# stoneWeather.net
KiCad netlist of a schematic drawn in EAGLE
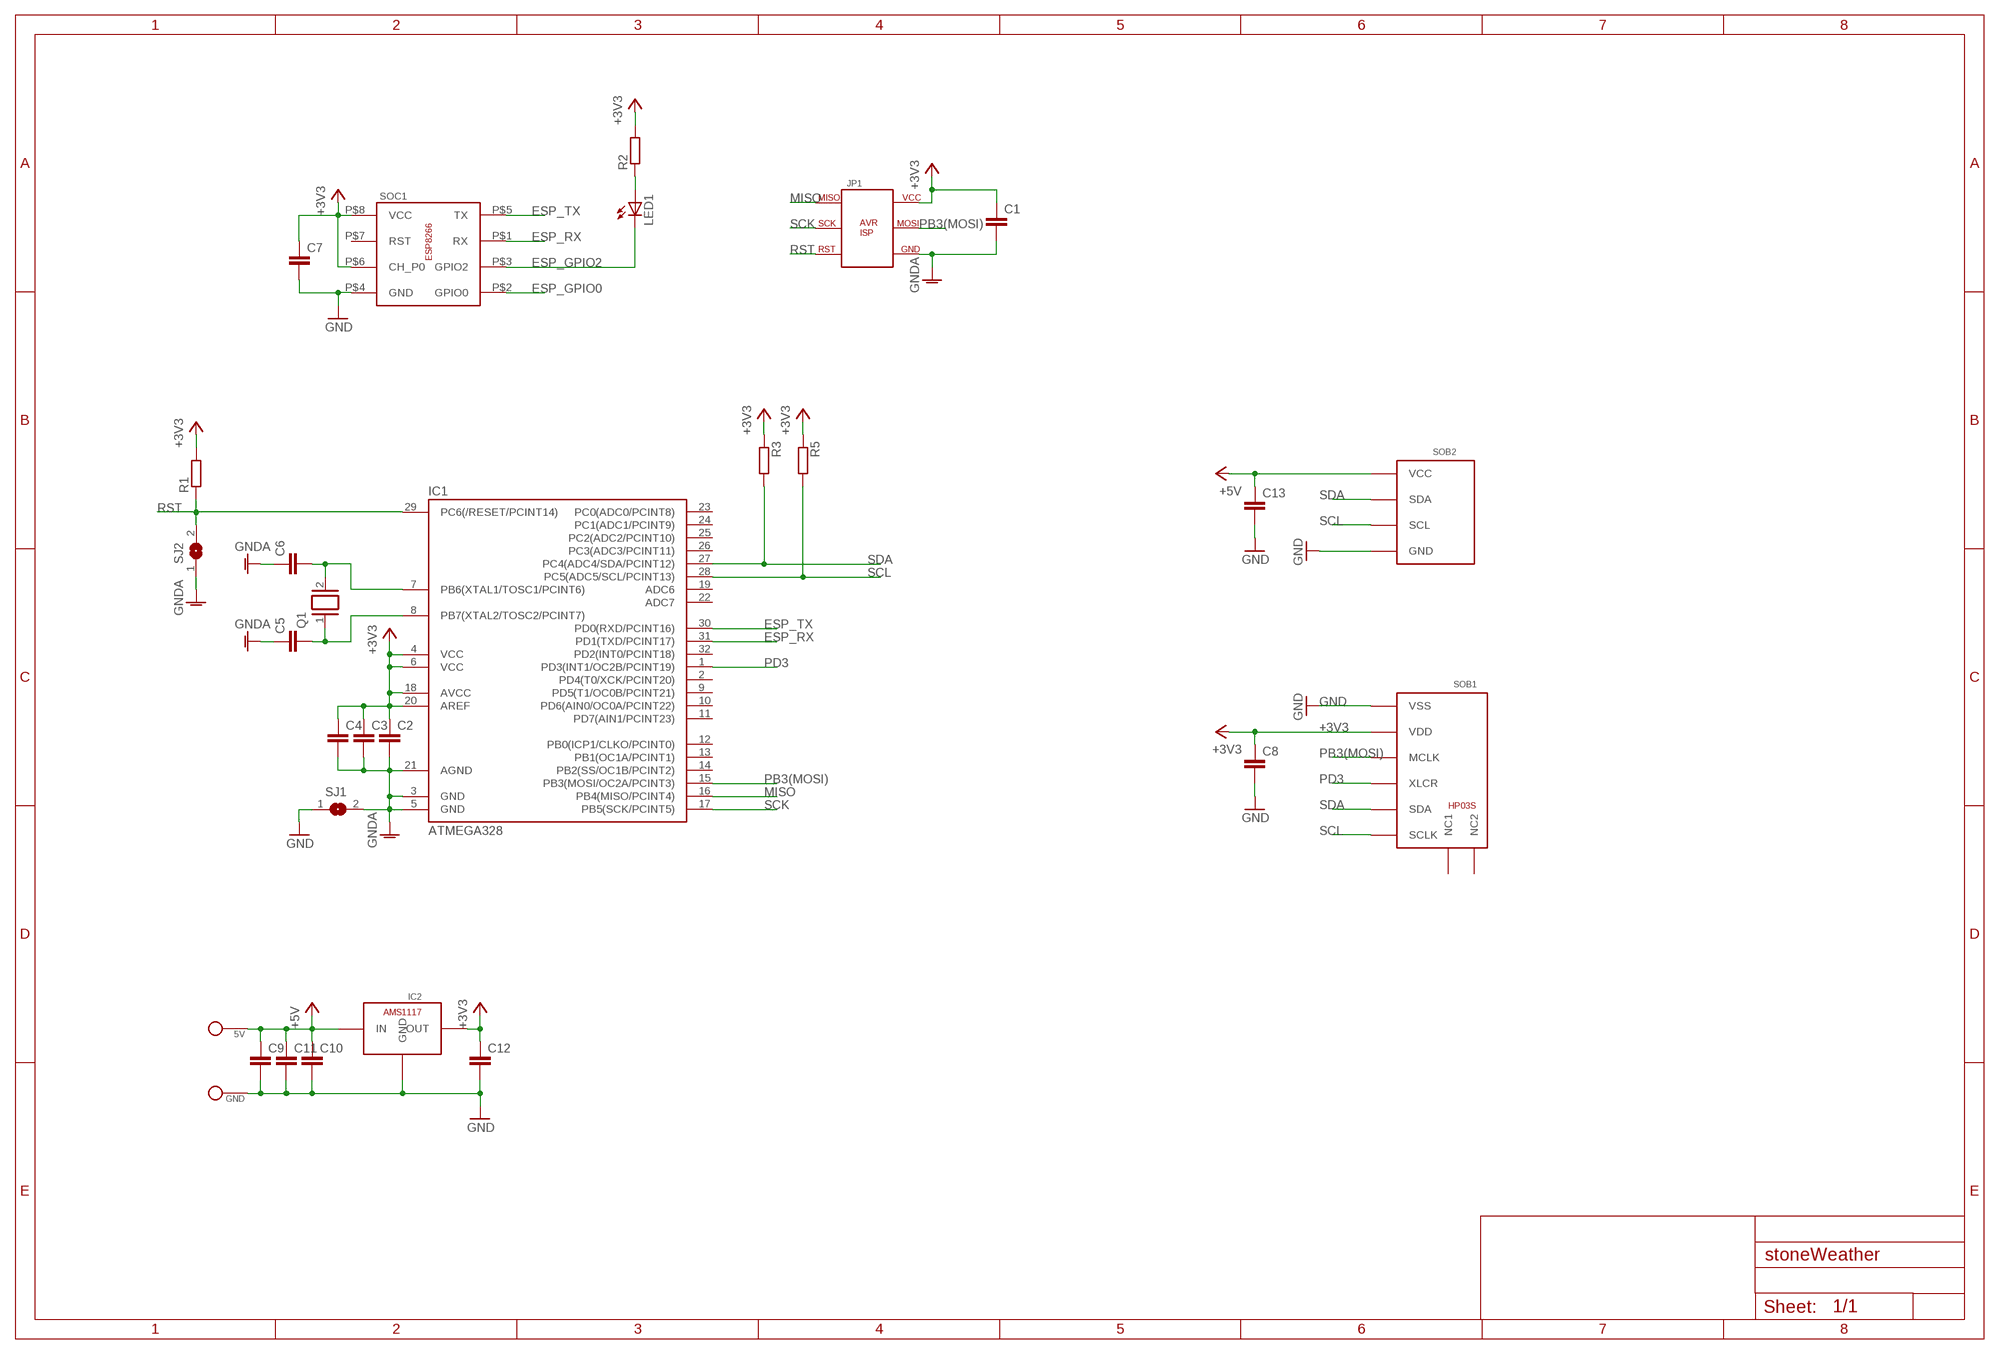
[diagram p0: schematic, sheet 1]

(export (version "E")
  (design (tool "Eeschema 10.0.6"))
  (components
    (comp (ref "5V")
      (value "PAD_254X508")
      (footprint "eagle-import:PAD_254X508")
      (libsource (lib "eagle-import") (part "PAD_254X508"))
    )
    (comp (ref "C1")
      (value "C-EUC0805")
      (footprint "eagle-import:C0805")
      (libsource (lib "eagle-import") (part "C-EUC0805"))
    )
    (comp (ref "C2")
      (value "C-EUC0805")
      (footprint "eagle-import:C0805")
      (libsource (lib "eagle-import") (part "C-EUC0805"))
    )
    (comp (ref "C3")
      (value "C-EUC0805")
      (footprint "eagle-import:C0805")
      (libsource (lib "eagle-import") (part "C-EUC0805"))
    )
    (comp (ref "C4")
      (value "C-EUC0805")
      (footprint "eagle-import:C0805")
      (libsource (lib "eagle-import") (part "C-EUC0805"))
    )
    (comp (ref "C5")
      (value "C-EUC0805")
      (footprint "eagle-import:C0805")
      (libsource (lib "eagle-import") (part "C-EUC0805"))
    )
    (comp (ref "C6")
      (value "C-EUC0805")
      (footprint "eagle-import:C0805")
      (libsource (lib "eagle-import") (part "C-EUC0805"))
    )
    (comp (ref "C7")
      (value "C-EUC0805")
      (footprint "eagle-import:C0805")
      (libsource (lib "eagle-import") (part "C-EUC0805"))
    )
    (comp (ref "C8")
      (value "C-EUC0805")
      (footprint "eagle-import:C0805")
      (libsource (lib "eagle-import") (part "C-EUC0805"))
    )
    (comp (ref "C9")
      (value "C-EUC0805")
      (footprint "eagle-import:C0805")
      (libsource (lib "eagle-import") (part "C-EUC0805"))
    )
    (comp (ref "C10")
      (value "C-EUC0805")
      (footprint "eagle-import:C0805")
      (libsource (lib "eagle-import") (part "C-EUC0805"))
    )
    (comp (ref "C11")
      (value "C-EUC0805")
      (footprint "eagle-import:C0805")
      (libsource (lib "eagle-import") (part "C-EUC0805"))
    )
    (comp (ref "C12")
      (value "C-EUC0805")
      (footprint "eagle-import:C0805")
      (libsource (lib "eagle-import") (part "C-EUC0805"))
    )
    (comp (ref "C13")
      (value "C-EUC0805")
      (footprint "eagle-import:C0805")
      (libsource (lib "eagle-import") (part "C-EUC0805"))
    )
    (comp (ref "GND")
      (value "PAD_254X508")
      (footprint "eagle-import:PAD_254X508")
      (libsource (lib "eagle-import") (part "PAD_254X508"))
    )
    (comp (ref "IC1")
      (value "ATMEGA328")
      (footprint "eagle-import:TQFP32-08")
      (libsource (lib "eagle-import") (part "ATMEGA48/88/168-AU"))
    )
    (comp (ref "IC2")
      (value "AMS1117")
      (footprint "eagle-import:AMS1117")
      (libsource (lib "eagle-import") (part "AMS1117"))
    )
    (comp (ref "JP1")
      (value "AVR_ISPSINGLESIDED_SMD")
      (footprint "eagle-import:PINHEADER_254_2X3_SMD")
      (libsource (lib "eagle-import") (part "AVR_ISPSINGLESIDED_SMD"))
    )
    (comp (ref "LED1")
      (value "LED3MM")
      (footprint "eagle-import:LED3MM")
      (libsource (lib "eagle-import") (part "LED3MM"))
    )
    (comp (ref "Q1")
      (value "XTAL/S")
      (footprint "eagle-import:QS")
      (libsource (lib "eagle-import") (part "XTAL/S"))
    )
    (comp (ref "R1")
      (value "R-EU_M0805")
      (footprint "eagle-import:M0805")
      (libsource (lib "eagle-import") (part "R-EU_M0805"))
    )
    (comp (ref "R2")
      (value "R-EU_M0805")
      (footprint "eagle-import:M0805")
      (libsource (lib "eagle-import") (part "R-EU_M0805"))
    )
    (comp (ref "R3")
      (value "R-EU_M0805")
      (footprint "eagle-import:M0805")
      (libsource (lib "eagle-import") (part "R-EU_M0805"))
    )
    (comp (ref "R5")
      (value "R-EU_M0805")
      (footprint "eagle-import:M0805")
      (libsource (lib "eagle-import") (part "R-EU_M0805"))
    )
    (comp (ref "SJ1") (value "SJ") (footprint "eagle-import:SJ") (libsource (lib "eagle-import") (part "SJ")))
    (comp (ref "SJ2") (value "SJ") (footprint "eagle-import:SJ") (libsource (lib "eagle-import") (part "SJ")))
    (comp (ref "SOB1")
      (value "HP03S")
      (footprint "eagle-import:HP03S")
      (libsource (lib "eagle-import") (part "HP03S"))
    )
    (comp (ref "SOB2")
      (value "GY21_HTU21")
      (footprint "eagle-import:GY21-HTU21")
      (libsource (lib "eagle-import") (part "GY21_HTU21"))
    )
    (comp (ref "SOC1")
      (value "ESP8266PINHEADER_SMD")
      (footprint "eagle-import:ESP8266")
      (libsource (lib "eagle-import") (part "ESP8266PINHEADER_SMD"))
    )
  )
  (nets
    (net (code "1") (name "+3V3") (class "Default")
      (node (ref "C1") (pin "1") (pinfunction "1_1") (pintype "passive"))
      (node (ref "C12") (pin "1") (pinfunction "1_1") (pintype "passive"))
      (node (ref "C2") (pin "1") (pinfunction "1_1") (pintype "passive"))
      (node (ref "C3") (pin "1") (pinfunction "1_1") (pintype "passive"))
      (node (ref "C4") (pin "1") (pinfunction "1_1") (pintype "passive"))
      (node (ref "C7") (pin "1") (pinfunction "1_1") (pintype "passive"))
      (node (ref "C8") (pin "1") (pinfunction "1_1") (pintype "passive"))
      (node (ref "IC1") (pin "18") (pinfunction "AVCC_18") (pintype "passive"))
      (node (ref "IC1") (pin "20") (pinfunction "AREF_20") (pintype "passive"))
      (node (ref "IC1") (pin "4") (pinfunction "VCC_4") (pintype "power_in"))
      (node (ref "IC1") (pin "6") (pinfunction "VCC_6") (pintype "power_in"))
      (node (ref "IC2") (pin "OUT") (pinfunction "OUT_OUT") (pintype "bidirectional"))
      (node (ref "JP1") (pin "P$8") (pinfunction "VCC_P$8") (pintype "bidirectional"))
      (node (ref "R1") (pin "2") (pinfunction "2_2") (pintype "passive"))
      (node (ref "R2") (pin "2") (pinfunction "2_2") (pintype "passive"))
      (node (ref "R3") (pin "1") (pinfunction "1_1") (pintype "passive"))
      (node (ref "R5") (pin "1") (pinfunction "1_1") (pintype "passive"))
      (node (ref "SOB1") (pin "VDD") (pinfunction "VDD_VDD") (pintype "bidirectional"))
      (node (ref "SOC1") (pin "P$6") (pinfunction "CH_P0_P$6") (pintype "bidirectional"))
      (node (ref "SOC1") (pin "P$8") (pinfunction "VCC_P$8") (pintype "bidirectional"))
    )
    (net (code "2") (name "+5V") (class "Default")
      (node (ref "5V") (pin "P$1") (pinfunction "P$1_P$1") (pintype "bidirectional"))
      (node (ref "C10") (pin "1") (pinfunction "1_1") (pintype "passive"))
      (node (ref "C11") (pin "1") (pinfunction "1_1") (pintype "passive"))
      (node (ref "C13") (pin "1") (pinfunction "1_1") (pintype "passive"))
      (node (ref "C9") (pin "1") (pinfunction "1_1") (pintype "passive"))
      (node (ref "IC2") (pin "IN") (pinfunction "IN_IN") (pintype "bidirectional"))
      (node (ref "SOB2") (pin "P$4") (pinfunction "VCC_P$4") (pintype "bidirectional"))
    )
    (net (code "3") (name "/ESP_GPIO0") (class "Default")
      (node (ref "SOC1") (pin "P$2") (pinfunction "GPIO0_P$2") (pintype "bidirectional"))
    )
    (net (code "4") (name "/ESP_GPIO2") (class "Default")
      (node (ref "LED1") (pin "K") (pinfunction "C_K") (pintype "passive"))
      (node (ref "SOC1") (pin "P$3") (pinfunction "GPIO2_P$3") (pintype "bidirectional"))
    )
    (net (code "5") (name "/ESP_RX") (class "Default")
      (node (ref "IC1") (pin "31") (pinfunction "PD1(TXD/PCINT17)_31") (pintype "bidirectional"))
      (node (ref "SOC1") (pin "P$1") (pinfunction "RX_P$1") (pintype "bidirectional"))
    )
    (net (code "6") (name "/ESP_TX") (class "Default")
      (node (ref "IC1") (pin "30") (pinfunction "PD0(RXD/PCINT16)_30") (pintype "bidirectional"))
      (node (ref "SOC1") (pin "P$5") (pinfunction "TX_P$5") (pintype "bidirectional"))
    )
    (net (code "7") (name "/MISO") (class "Default")
      (node (ref "IC1") (pin "16") (pinfunction "PB4(MISO/PCINT4)_16") (pintype "bidirectional"))
      (node (ref "JP1") (pin "P$1") (pinfunction "MISO_P$1") (pintype "bidirectional"))
    )
    (net (code "8") (name "/PB3(MOSI)") (class "Default")
      (node (ref "IC1") (pin "15") (pinfunction "PB3(MOSI/OC2A/PCINT3)_15") (pintype "bidirectional"))
      (node (ref "JP1") (pin "P$7") (pinfunction "MOSI_P$7") (pintype "bidirectional"))
      (node (ref "SOB1") (pin "MCLK") (pinfunction "MCLK_MCLK") (pintype "bidirectional"))
    )
    (net (code "9") (name "/PD3") (class "Default")
      (node (ref "IC1") (pin "1") (pinfunction "PD3(INT1/OC2B/PCINT19)_1") (pintype "bidirectional"))
      (node (ref "SOB1") (pin "XCLR") (pinfunction "XLCR_XCLR") (pintype "bidirectional"))
    )
    (net (code "10") (name "/RST") (class "Default")
      (node (ref "IC1") (pin "29") (pinfunction "PC6(/RESET/PCINT14)_29") (pintype "bidirectional"))
      (node (ref "JP1") (pin "P$3") (pinfunction "RST_P$3") (pintype "bidirectional"))
      (node (ref "R1") (pin "1") (pinfunction "1_1") (pintype "passive"))
      (node (ref "SJ2") (pin "2") (pinfunction "2_2") (pintype "passive"))
    )
    (net (code "11") (name "/SCK") (class "Default")
      (node (ref "IC1") (pin "17") (pinfunction "PB5(SCK/PCINT5)_17") (pintype "bidirectional"))
      (node (ref "JP1") (pin "P$2") (pinfunction "SCK_P$2") (pintype "bidirectional"))
    )
    (net (code "12") (name "/SCL") (class "Default")
      (node (ref "IC1") (pin "28") (pinfunction "PC5(ADC5/SCL/PCINT13)_28") (pintype "bidirectional"))
      (node (ref "R5") (pin "2") (pinfunction "2_2") (pintype "passive"))
      (node (ref "SOB1") (pin "SCLK") (pinfunction "SCLK_SCLK") (pintype "bidirectional"))
      (node (ref "SOB2") (pin "P$2") (pinfunction "SCL_P$2") (pintype "bidirectional"))
    )
    (net (code "13") (name "/SDA") (class "Default")
      (node (ref "IC1") (pin "27") (pinfunction "PC4(ADC4/SDA/PCINT12)_27") (pintype "bidirectional"))
      (node (ref "R3") (pin "2") (pinfunction "2_2") (pintype "passive"))
      (node (ref "SOB1") (pin "SDA") (pinfunction "SDA_SDA") (pintype "bidirectional"))
      (node (ref "SOB2") (pin "P$1") (pinfunction "SDA_P$1") (pintype "bidirectional"))
    )
    (net (code "14") (name "GND") (class "Default")
      (node (ref "C10") (pin "2") (pinfunction "2_2") (pintype "passive"))
      (node (ref "C11") (pin "2") (pinfunction "2_2") (pintype "passive"))
      (node (ref "C12") (pin "2") (pinfunction "2_2") (pintype "passive"))
      (node (ref "C13") (pin "2") (pinfunction "2_2") (pintype "passive"))
      (node (ref "C7") (pin "2") (pinfunction "2_2") (pintype "passive"))
      (node (ref "C8") (pin "2") (pinfunction "2_2") (pintype "passive"))
      (node (ref "C9") (pin "2") (pinfunction "2_2") (pintype "passive"))
      (node (ref "GND") (pin "P$1") (pinfunction "P$1_P$1") (pintype "bidirectional"))
      (node (ref "IC2") (pin "GND") (pinfunction "GND_GND") (pintype "bidirectional"))
      (node (ref "SJ1") (pin "1") (pinfunction "1_1") (pintype "passive"))
      (node (ref "SOB1") (pin "VSS") (pinfunction "VSS_VSS") (pintype "bidirectional"))
      (node (ref "SOB2") (pin "P$3") (pinfunction "GND_P$3") (pintype "bidirectional"))
      (node (ref "SOC1") (pin "P$4") (pinfunction "GND_P$4") (pintype "bidirectional"))
    )
    (net (code "15") (name "GNDA") (class "Default")
      (node (ref "C1") (pin "2") (pinfunction "2_2") (pintype "passive"))
      (node (ref "C2") (pin "2") (pinfunction "2_2") (pintype "passive"))
      (node (ref "C3") (pin "2") (pinfunction "2_2") (pintype "passive"))
      (node (ref "C4") (pin "2") (pinfunction "2_2") (pintype "passive"))
      (node (ref "C5") (pin "1") (pinfunction "1_1") (pintype "passive"))
      (node (ref "C6") (pin "1") (pinfunction "1_1") (pintype "passive"))
      (node (ref "IC1") (pin "21") (pinfunction "AGND_21") (pintype "power_in"))
      (node (ref "IC1") (pin "3") (pinfunction "GND_3") (pintype "power_in"))
      (node (ref "IC1") (pin "5") (pinfunction "GND_5") (pintype "power_in"))
      (node (ref "JP1") (pin "P$6") (pinfunction "GND_P$6") (pintype "bidirectional"))
      (node (ref "SJ1") (pin "2") (pinfunction "2_2") (pintype "passive"))
      (node (ref "SJ2") (pin "1") (pinfunction "1_1") (pintype "passive"))
    )
    (net (code "16") (name "Net-(IC1-PB6(XTAL1{slash}TOSC1{slash}PCINT6))") (class "Default")
      (node (ref "C6") (pin "2") (pinfunction "2_2") (pintype "passive"))
      (node (ref "IC1") (pin "7") (pinfunction "PB6(XTAL1/TOSC1/PCINT6)_7") (pintype "bidirectional"))
      (node (ref "Q1") (pin "2") (pinfunction "2_2") (pintype "passive"))
    )
    (net (code "17") (name "Net-(IC1-PB7(XTAL2{slash}TOSC2{slash}PCINT7))") (class "Default")
      (node (ref "C5") (pin "2") (pinfunction "2_2") (pintype "passive"))
      (node (ref "IC1") (pin "8") (pinfunction "PB7(XTAL2/TOSC2/PCINT7)_8") (pintype "bidirectional"))
      (node (ref "Q1") (pin "1") (pinfunction "1_1") (pintype "passive"))
    )
    (net (code "18") (name "Net-(LED1-PadA)") (class "Default")
      (node (ref "LED1") (pin "A") (pinfunction "A_A") (pintype "passive"))
      (node (ref "R2") (pin "1") (pinfunction "1_1") (pintype "passive"))
    )
    (net (code "19") (name "unconnected-(IC1-ADC6-Pad19)") (class "Default")
      (node (ref "IC1") (pin "19") (pinfunction "ADC6_19") (pintype "passive"))
    )
    (net (code "20") (name "unconnected-(IC1-ADC7-Pad22)") (class "Default")
      (node (ref "IC1") (pin "22") (pinfunction "ADC7_22") (pintype "passive"))
    )
    (net (code "21") (name "unconnected-(IC1-PB0(ICP1{slash}CLKO{slash}PCINT0)-Pad12)") (class "Default")
      (node (ref "IC1") (pin "12") (pinfunction "PB0(ICP1/CLKO/PCINT0)_12") (pintype "bidirectional"))
    )
    (net (code "22") (name "unconnected-(IC1-PB1(OC1A{slash}PCINT1)-Pad13)") (class "Default")
      (node (ref "IC1") (pin "13") (pinfunction "PB1(OC1A/PCINT1)_13") (pintype "bidirectional"))
    )
    (net (code "23") (name "unconnected-(IC1-PB2(SS{slash}OC1B{slash}PCINT2)-Pad14)") (class "Default")
      (node (ref "IC1") (pin "14") (pinfunction "PB2(SS/OC1B/PCINT2)_14") (pintype "bidirectional"))
    )
    (net (code "24") (name "unconnected-(IC1-PC0(ADC0{slash}PCINT8)-Pad23)") (class "Default")
      (node (ref "IC1") (pin "23") (pinfunction "PC0(ADC0/PCINT8)_23") (pintype "bidirectional"))
    )
    (net (code "25") (name "unconnected-(IC1-PC1(ADC1{slash}PCINT9)-Pad24)") (class "Default")
      (node (ref "IC1") (pin "24") (pinfunction "PC1(ADC1/PCINT9)_24") (pintype "bidirectional"))
    )
    (net (code "26") (name "unconnected-(IC1-PC2(ADC2{slash}PCINT10)-Pad25)") (class "Default")
      (node (ref "IC1") (pin "25") (pinfunction "PC2(ADC2/PCINT10)_25") (pintype "bidirectional"))
    )
    (net (code "27") (name "unconnected-(IC1-PC3(ADC3{slash}PCINT11)-Pad26)") (class "Default")
      (node (ref "IC1") (pin "26") (pinfunction "PC3(ADC3/PCINT11)_26") (pintype "bidirectional"))
    )
    (net (code "28") (name "unconnected-(IC1-PD2(INT0{slash}PCINT18)-Pad32)") (class "Default")
      (node (ref "IC1") (pin "32") (pinfunction "PD2(INT0/PCINT18)_32") (pintype "bidirectional"))
    )
    (net (code "29") (name "unconnected-(IC1-PD4(T0{slash}XCK{slash}PCINT20)-Pad2)") (class "Default")
      (node (ref "IC1") (pin "2") (pinfunction "PD4(T0/XCK/PCINT20)_2") (pintype "bidirectional"))
    )
    (net (code "30") (name "unconnected-(IC1-PD5(T1{slash}OC0B{slash}PCINT21)-Pad9)") (class "Default")
      (node (ref "IC1") (pin "9") (pinfunction "PD5(T1/OC0B/PCINT21)_9") (pintype "bidirectional"))
    )
    (net (code "31") (name "unconnected-(IC1-PD6(AIN0{slash}OC0A{slash}PCINT22)-Pad10)") (class "Default")
      (node (ref "IC1") (pin "10") (pinfunction "PD6(AIN0/OC0A/PCINT22)_10") (pintype "bidirectional"))
    )
    (net (code "32") (name "unconnected-(IC1-PD7(AIN1{slash}PCINT23)-Pad11)") (class "Default")
      (node (ref "IC1") (pin "11") (pinfunction "PD7(AIN1/PCINT23)_11") (pintype "bidirectional"))
    )
    (net (code "33") (name "unconnected-(SOB1-PadNC1)") (class "Default")
      (node (ref "SOB1") (pin "NC1") (pinfunction "NC1_NC1") (pintype "bidirectional"))
    )
    (net (code "34") (name "unconnected-(SOB1-PadNC2)") (class "Default")
      (node (ref "SOB1") (pin "NC2") (pinfunction "NC2_NC2") (pintype "bidirectional"))
    )
    (net (code "35") (name "unconnected-(SOC1-RST-PadP$7)") (class "Default")
      (node (ref "SOC1") (pin "P$7") (pinfunction "RST_P$7") (pintype "bidirectional"))
    )
  )
)
